# compute_module.net
KiCad netlist of a schematic drawn in Altium Designer
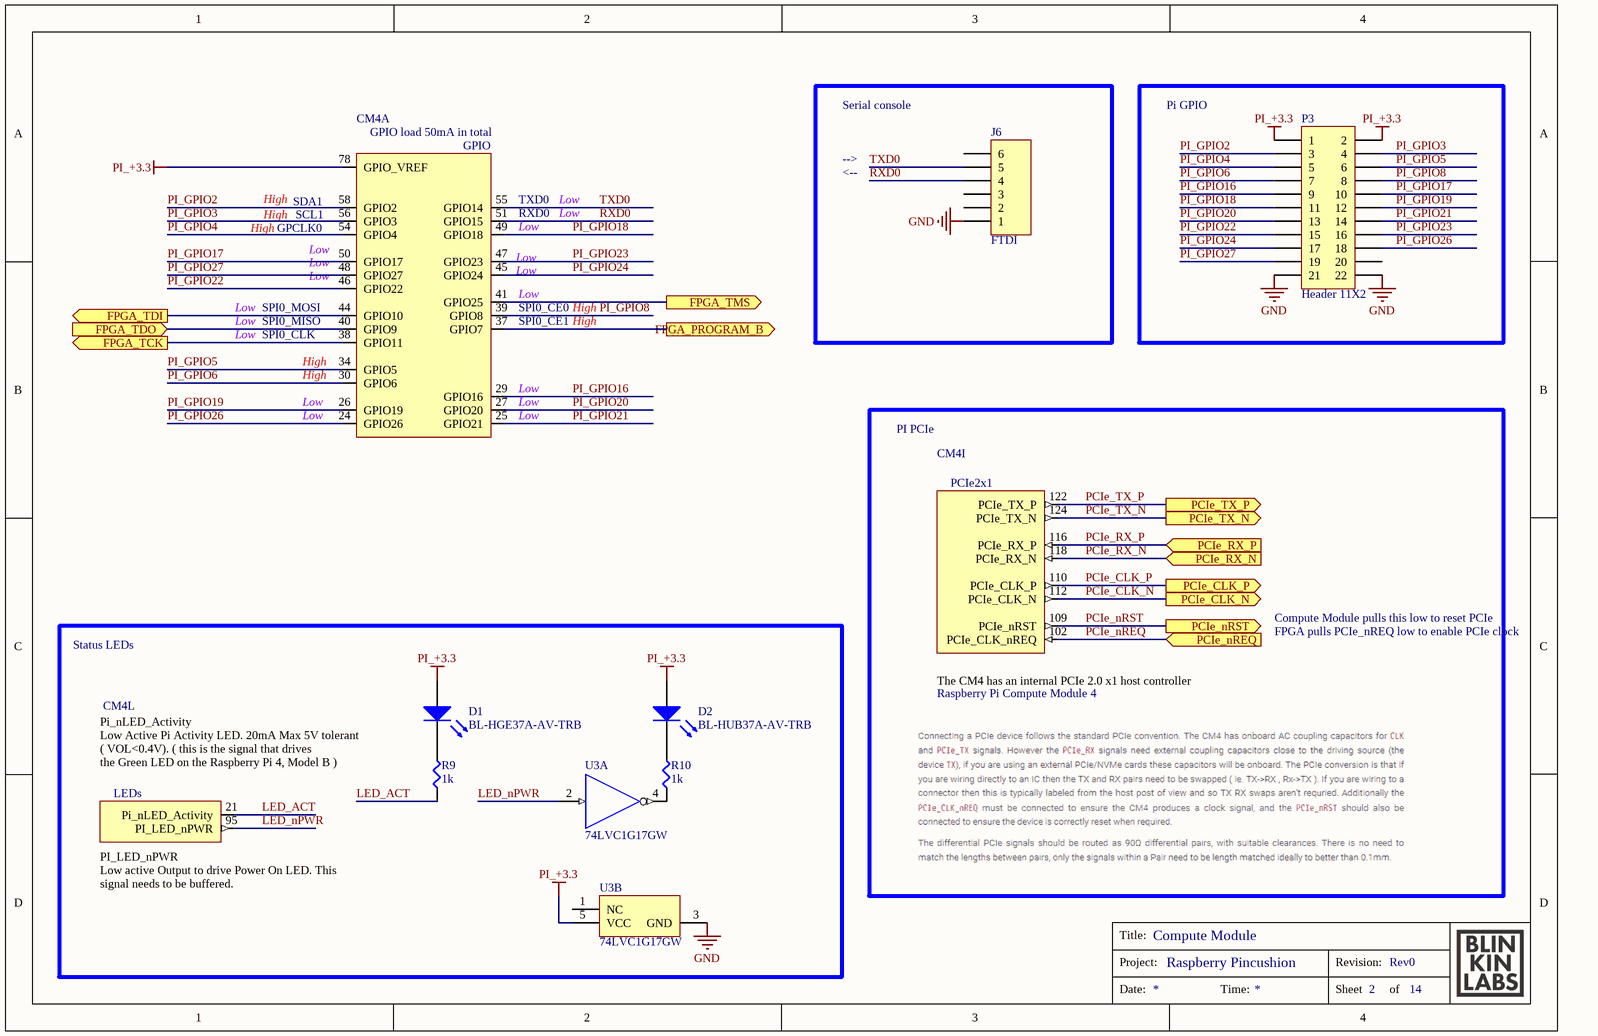
[diagram p0: compute module.SchDoc]

(export (version "E")
  (design (tool "Eeschema 10.0.6"))
  (components
    (comp (ref "CM4")
      (value "Raspberry Pi Compute Module 4")
      (footprint "CM4-F40C-100DS-0.4v_1.5mm_0mm")
      (description "Raspberry Pi Compute Module 4 by Amornthep Phunsin")
      (libsource (lib "CM4") (part "CM4"))
    )
    (comp (ref "D1")
      (value "BL-HGE37A-AV-TRB")
      (footprint "BL-Hxx37A-AV-TRB")
      (description "LED, 0402, Super Yellow Green, 35mcd@20mA, 566~576nm")
      (fields (field (name "MANUFACTURER") "BrtLed(佰鸿)") (field (name "LCSC PARTNUMBER") "C165979"))
      (libsource (lib "Blinkinlabs") (part "BL-HGE37A-AV-TRB"))
    )
    (comp (ref "D2")
      (value "BL-HUB37A-AV-TRB")
      (footprint "BL-Hxx37A-AV-TRB")
      (description "LED, 0402, Super Red, 50mcd@20mA, 627~637nm")
      (fields (field (name "MANUFACTURER") "BrtLed(佰鸿)") (field (name "LCSC PARTNUMBER") "C165980"))
      (libsource (lib "Blinkinlabs") (part "BL-HUB37A-AV-TRB"))
    )
    (comp (ref "J6")
      (value "FTDI")
      (footprint "HDR1X6")
      (description "Header, 6-Pin")
      (fields (field (name "PUBLISHER") "Altium Limited"))
      (libsource (lib "Miscellaneous Connectors") (part "Header 6"))
    )
    (comp (ref "P3")
      (value "Header 11X2")
      (footprint "HDR2X11")
      (description "Header, 11-Pin, Dual row")
      (fields (field (name "PUBLISHER") "Altium Limited"))
      (libsource (lib "Miscellaneous Connectors") (part "Header 11X2"))
    )
    (comp (ref "R9")
      (value "1k")
      (footprint "ERJ2G(0402)_L")
      (description "RES SMD 1K OHM 5% 1/10W 0402")
      (fields (field (name "PARTNUMBER") "ERJ-2GEJ102X") (field (name "DIGI-KEY PART NUMBER") "P1.0KJCT-ND"))
      (libsource (lib "res_panasonic_erj_xls") (part "RESISTOR"))
    )
    (comp (ref "R10")
      (value "1k")
      (footprint "ERJ2G(0402)_L")
      (description "RES SMD 1K OHM 5% 1/10W 0402")
      (fields (field (name "PARTNUMBER") "ERJ-2GEJ102X") (field (name "DIGI-KEY PART NUMBER") "P1.0KJCT-ND"))
      (libsource (lib "res_panasonic_erj_xls") (part "RESISTOR"))
    )
    (comp (ref "U3")
      (value "74LVC1G17GW")
      (footprint "NXP-SOT353-1_L")
      (fields (field (name "MANUFACTURER") "NXP Semiconductors"))
      (libsource (lib "Altium Content Vault") (part "NXP-74LVC1G17-5"))
    )
  )
  (nets
    (net (code "1") (name "/FPGA_PROGRAM_B") (class "Default")
      (node (ref "CM4") (pin "37") (pinfunction "GPIO7_37") (pintype "passive"))
    )
    (net (code "2") (name "/FPGA_TCK") (class "Default")
      (node (ref "CM4") (pin "38") (pinfunction "GPIO11_38") (pintype "passive"))
    )
    (net (code "3") (name "/FPGA_TDI") (class "Default")
      (node (ref "CM4") (pin "44") (pinfunction "GPIO10_44") (pintype "passive"))
    )
    (net (code "4") (name "/FPGA_TDO") (class "Default")
      (node (ref "CM4") (pin "40") (pinfunction "GPIO9_40") (pintype "passive"))
    )
    (net (code "5") (name "/FPGA_TMS") (class "Default")
      (node (ref "CM4") (pin "41") (pinfunction "GPIO25_41") (pintype "passive"))
    )
    (net (code "6") (name "/LED_ACT") (class "Default")
      (node (ref "CM4") (pin "21") (pinfunction "Pi_nLED_Activity_21") (pintype "open_collector"))
      (node (ref "R9") (pin "1") (pinfunction "1_1") (pintype "passive"))
    )
    (net (code "7") (name "/LED_nPWR") (class "Default")
      (node (ref "CM4") (pin "95") (pinfunction "PI_LED_nPWR_95") (pintype "output"))
      (node (ref "U3") (pin "2") (pinfunction "A_2") (pintype "input"))
    )
    (net (code "8") (name "/PCIe_CLK_N") (class "Default")
      (node (ref "CM4") (pin "112") (pinfunction "PCIe_CLK_N_112") (pintype "output"))
    )
    (net (code "9") (name "/PCIe_CLK_P") (class "Default")
      (node (ref "CM4") (pin "110") (pinfunction "PCIe_CLK_P_110") (pintype "output"))
    )
    (net (code "10") (name "/PCIe_RX_N") (class "Default")
      (node (ref "CM4") (pin "118") (pinfunction "PCIe_RX_N_118") (pintype "input"))
    )
    (net (code "11") (name "/PCIe_RX_P") (class "Default")
      (node (ref "CM4") (pin "116") (pinfunction "PCIe_RX_P_116") (pintype "input"))
    )
    (net (code "12") (name "/PCIe_TX_N") (class "Default")
      (node (ref "CM4") (pin "124") (pinfunction "PCIe_TX_N_124") (pintype "output"))
    )
    (net (code "13") (name "/PCIe_TX_P") (class "Default")
      (node (ref "CM4") (pin "122") (pinfunction "PCIe_TX_P_122") (pintype "output"))
    )
    (net (code "14") (name "/PCIe_nREQ") (class "Default")
      (node (ref "CM4") (pin "102") (pinfunction "PCIe_CLK_nREQ_102") (pintype "input"))
    )
    (net (code "15") (name "/PCIe_nRST") (class "Default")
      (node (ref "CM4") (pin "109") (pinfunction "PCIe_nRST_109") (pintype "output"))
    )
    (net (code "16") (name "/PI_GPIO2") (class "Default")
      (node (ref "CM4") (pin "58") (pinfunction "GPIO2_58") (pintype "passive"))
      (node (ref "P3") (pin "3") (pinfunction "3_3") (pintype "passive"))
    )
    (net (code "17") (name "/PI_GPIO3") (class "Default")
      (node (ref "CM4") (pin "56") (pinfunction "GPIO3_56") (pintype "passive"))
      (node (ref "P3") (pin "4") (pinfunction "4_4") (pintype "passive"))
    )
    (net (code "18") (name "/PI_GPIO4") (class "Default")
      (node (ref "CM4") (pin "54") (pinfunction "GPIO4_54") (pintype "passive"))
      (node (ref "P3") (pin "5") (pinfunction "5_5") (pintype "passive"))
    )
    (net (code "19") (name "/PI_GPIO5") (class "Default")
      (node (ref "CM4") (pin "34") (pinfunction "GPIO5_34") (pintype "passive"))
      (node (ref "P3") (pin "6") (pinfunction "6_6") (pintype "passive"))
    )
    (net (code "20") (name "/PI_GPIO6") (class "Default")
      (node (ref "CM4") (pin "30") (pinfunction "GPIO6_30") (pintype "passive"))
      (node (ref "P3") (pin "7") (pinfunction "7_7") (pintype "passive"))
    )
    (net (code "21") (name "/PI_GPIO8") (class "Default")
      (node (ref "CM4") (pin "39") (pinfunction "GPIO8_39") (pintype "passive"))
      (node (ref "P3") (pin "8") (pinfunction "8_8") (pintype "passive"))
    )
    (net (code "22") (name "/PI_GPIO16") (class "Default")
      (node (ref "CM4") (pin "29") (pinfunction "GPIO16_29") (pintype "passive"))
      (node (ref "P3") (pin "9") (pinfunction "9_9") (pintype "passive"))
    )
    (net (code "23") (name "/PI_GPIO17") (class "Default")
      (node (ref "CM4") (pin "50") (pinfunction "GPIO17_50") (pintype "passive"))
      (node (ref "P3") (pin "10") (pinfunction "10_10") (pintype "passive"))
    )
    (net (code "24") (name "/PI_GPIO18") (class "Default")
      (node (ref "CM4") (pin "49") (pinfunction "GPIO18_49") (pintype "passive"))
      (node (ref "P3") (pin "11") (pinfunction "11_11") (pintype "passive"))
    )
    (net (code "25") (name "/PI_GPIO19") (class "Default")
      (node (ref "CM4") (pin "26") (pinfunction "GPIO19_26") (pintype "passive"))
      (node (ref "P3") (pin "12") (pinfunction "12_12") (pintype "passive"))
    )
    (net (code "26") (name "/PI_GPIO20") (class "Default")
      (node (ref "CM4") (pin "27") (pinfunction "GPIO20_27") (pintype "passive"))
      (node (ref "P3") (pin "13") (pinfunction "13_13") (pintype "passive"))
    )
    (net (code "27") (name "/PI_GPIO21") (class "Default")
      (node (ref "CM4") (pin "25") (pinfunction "GPIO21_25") (pintype "passive"))
      (node (ref "P3") (pin "14") (pinfunction "14_14") (pintype "passive"))
    )
    (net (code "28") (name "/PI_GPIO22") (class "Default")
      (node (ref "CM4") (pin "46") (pinfunction "GPIO22_46") (pintype "passive"))
      (node (ref "P3") (pin "15") (pinfunction "15_15") (pintype "passive"))
    )
    (net (code "29") (name "/PI_GPIO23") (class "Default")
      (node (ref "CM4") (pin "47") (pinfunction "GPIO23_47") (pintype "passive"))
      (node (ref "P3") (pin "16") (pinfunction "16_16") (pintype "passive"))
    )
    (net (code "30") (name "/PI_GPIO24") (class "Default")
      (node (ref "CM4") (pin "45") (pinfunction "GPIO24_45") (pintype "passive"))
      (node (ref "P3") (pin "17") (pinfunction "17_17") (pintype "passive"))
    )
    (net (code "31") (name "/PI_GPIO26") (class "Default")
      (node (ref "CM4") (pin "24") (pinfunction "GPIO26_24") (pintype "passive"))
      (node (ref "P3") (pin "18") (pinfunction "18_18") (pintype "passive"))
    )
    (net (code "32") (name "/PI_GPIO27") (class "Default")
      (node (ref "CM4") (pin "48") (pinfunction "GPIO27_48") (pintype "passive"))
      (node (ref "P3") (pin "19") (pinfunction "19_19") (pintype "passive"))
    )
    (net (code "33") (name "/RXD0") (class "Default")
      (node (ref "CM4") (pin "51") (pinfunction "GPIO15_51") (pintype "passive"))
      (node (ref "J6") (pin "4") (pinfunction "4_4") (pintype "passive"))
    )
    (net (code "34") (name "/TXD0") (class "Default")
      (node (ref "CM4") (pin "55") (pinfunction "GPIO14_55") (pintype "passive"))
      (node (ref "J6") (pin "5") (pinfunction "5_5") (pintype "passive"))
    )
    (net (code "35") (name "GND") (class "Default")
      (node (ref "J6") (pin "1") (pinfunction "1_1") (pintype "passive"))
      (node (ref "P3") (pin "21") (pinfunction "21_21") (pintype "passive"))
      (node (ref "P3") (pin "22") (pinfunction "22_22") (pintype "passive"))
      (node (ref "U3") (pin "3") (pinfunction "GND_3") (pintype "power_in"))
    )
    (net (code "36") (name "Net-(D1-Pad2)") (class "Default")
      (node (ref "D1") (pin "2") (pinfunction "2_2") (pintype "passive"))
      (node (ref "R9") (pin "2") (pinfunction "2_2") (pintype "passive"))
    )
    (net (code "37") (name "Net-(D2-Pad2)") (class "Default")
      (node (ref "D2") (pin "2") (pinfunction "2_2") (pintype "passive"))
      (node (ref "R10") (pin "2") (pinfunction "2_2") (pintype "passive"))
    )
    (net (code "38") (name "Net-(U3A-~{Y})") (class "Default")
      (node (ref "R10") (pin "1") (pinfunction "1_1") (pintype "passive"))
      (node (ref "U3") (pin "4") (pinfunction "~{Y}_4") (pintype "output"))
    )
    (net (code "39") (name "PI_+3.3") (class "Default")
      (node (ref "CM4") (pin "78") (pinfunction "GPIO_VREF_78") (pintype "power_in"))
      (node (ref "D1") (pin "1") (pinfunction "1_1") (pintype "passive"))
      (node (ref "D2") (pin "1") (pinfunction "1_1") (pintype "passive"))
      (node (ref "P3") (pin "1") (pinfunction "1_1") (pintype "passive"))
      (node (ref "P3") (pin "2") (pinfunction "2_2") (pintype "passive"))
      (node (ref "U3") (pin "5") (pinfunction "VCC_5") (pintype "power_in"))
    )
    (net (code "40") (name "unconnected-(J6-Pad2)") (class "Default")
      (node (ref "J6") (pin "2") (pinfunction "2_2") (pintype "passive"))
    )
    (net (code "41") (name "unconnected-(J6-Pad3)") (class "Default")
      (node (ref "J6") (pin "3") (pinfunction "3_3") (pintype "passive"))
    )
    (net (code "42") (name "unconnected-(J6-Pad6)") (class "Default")
      (node (ref "J6") (pin "6") (pinfunction "6_6") (pintype "passive"))
    )
    (net (code "43") (name "unconnected-(P3-Pad20)") (class "Default")
      (node (ref "P3") (pin "20") (pinfunction "20_20") (pintype "passive"))
    )
    (net (code "44") (name "unconnected-(U3B-NC-Pad1)") (class "Default")
      (node (ref "U3") (pin "1") (pinfunction "NC_1") (pintype "passive"))
    )
  )
)
